# atmega.net
KiCad netlist of a schematic drawn in EAGLE
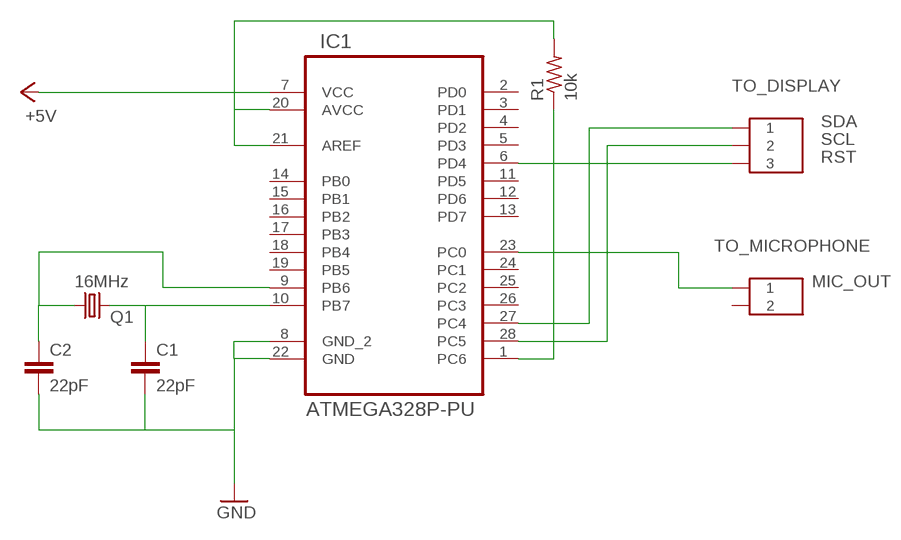
[diagram p0: schematic, sheet 1]

(export (version "E")
  (design (tool "Eeschema 10.0.6"))
  (components
    (comp (ref "C1")
      (value "22pF")
      (footprint "eagle-import:C025-024X044")
      (libsource (lib "eagle-import") (part "C-EU025-024X044"))
    )
    (comp (ref "C2")
      (value "22pF")
      (footprint "eagle-import:C025-024X044")
      (libsource (lib "eagle-import") (part "C-EU025-024X044"))
    )
    (comp (ref "IC1")
      (value "ATMEGA328P-PU")
      (footprint "eagle-import:DIP254P762X457-28")
      (libsource (lib "eagle-import") (part "ATMEGA328P-PU"))
    )
    (comp (ref "Q1")
      (value "16MHz")
      (footprint "eagle-import:86SMX")
      (libsource (lib "eagle-import") (part "CRYSTAL68SMX"))
    )
    (comp (ref "R1")
      (value "10k")
      (footprint "eagle-import:0204V")
      (libsource (lib "eagle-import") (part "R-US_0204/2V"))
    )
    (comp (ref "TO_DISPLAY")
      (value "EZG-00-303")
      (footprint "eagle-import:EZG-00-303")
      (libsource (lib "eagle-import") (part "EZG-?-30300"))
    )
    (comp (ref "TO_MICROPHONE")
      (value "EZG-00-302")
      (footprint "eagle-import:EZG-00-302")
      (libsource (lib "eagle-import") (part "EZG-?-30200"))
    )
  )
  (nets
    (net (code "1") (name "+5V") (class "Default")
      (node (ref "IC1") (pin "20") (pinfunction "AVCC_20") (pintype "power_in"))
      (node (ref "IC1") (pin "21") (pinfunction "AREF_21") (pintype "input"))
      (node (ref "IC1") (pin "7") (pinfunction "VCC_7") (pintype "power_in"))
      (node (ref "R1") (pin "2") (pinfunction "2_2") (pintype "passive"))
    )
    (net (code "2") (name "GND") (class "Default")
      (node (ref "C1") (pin "2") (pinfunction "2_2") (pintype "passive"))
      (node (ref "C2") (pin "2") (pinfunction "2_2") (pintype "passive"))
      (node (ref "IC1") (pin "22") (pinfunction "GND_22") (pintype "passive"))
      (node (ref "IC1") (pin "8") (pinfunction "GND_2_8") (pintype "passive"))
    )
    (net (code "3") (name "Net-(IC1-PB6)") (class "Default")
      (node (ref "C2") (pin "1") (pinfunction "1_1") (pintype "passive"))
      (node (ref "IC1") (pin "9") (pinfunction "PB6_9") (pintype "bidirectional"))
      (node (ref "Q1") (pin "1") (pinfunction "1_1") (pintype "passive"))
    )
    (net (code "4") (name "Net-(IC1-PB7)") (class "Default")
      (node (ref "C1") (pin "1") (pinfunction "1_1") (pintype "passive"))
      (node (ref "IC1") (pin "10") (pinfunction "PB7_10") (pintype "bidirectional"))
      (node (ref "Q1") (pin "4") (pinfunction "2_4") (pintype "passive"))
    )
    (net (code "5") (name "Net-(IC1-PC0)") (class "Default")
      (node (ref "IC1") (pin "23") (pinfunction "PC0_23") (pintype "bidirectional"))
      (node (ref "TO_MICROPHONE") (pin "1") (pinfunction "1_1") (pintype "passive"))
    )
    (net (code "6") (name "Net-(IC1-PC4)") (class "Default")
      (node (ref "IC1") (pin "27") (pinfunction "PC4_27") (pintype "bidirectional"))
      (node (ref "TO_DISPLAY") (pin "1") (pinfunction "1_1") (pintype "passive"))
    )
    (net (code "7") (name "Net-(IC1-PC5)") (class "Default")
      (node (ref "IC1") (pin "28") (pinfunction "PC5_28") (pintype "bidirectional"))
      (node (ref "TO_DISPLAY") (pin "2") (pinfunction "2_2") (pintype "passive"))
    )
    (net (code "8") (name "Net-(IC1-PC6)") (class "Default")
      (node (ref "IC1") (pin "1") (pinfunction "PC6_1") (pintype "bidirectional"))
      (node (ref "R1") (pin "1") (pinfunction "1_1") (pintype "passive"))
    )
    (net (code "9") (name "Net-(IC1-PD4)") (class "Default")
      (node (ref "IC1") (pin "6") (pinfunction "PD4_6") (pintype "bidirectional"))
      (node (ref "TO_DISPLAY") (pin "3") (pinfunction "3_3") (pintype "passive"))
    )
    (net (code "10") (name "unconnected-(IC1-PB0-Pad14)") (class "Default")
      (node (ref "IC1") (pin "14") (pinfunction "PB0_14") (pintype "bidirectional"))
    )
    (net (code "11") (name "unconnected-(IC1-PB1-Pad15)") (class "Default")
      (node (ref "IC1") (pin "15") (pinfunction "PB1_15") (pintype "bidirectional"))
    )
    (net (code "12") (name "unconnected-(IC1-PB2-Pad16)") (class "Default")
      (node (ref "IC1") (pin "16") (pinfunction "PB2_16") (pintype "bidirectional"))
    )
    (net (code "13") (name "unconnected-(IC1-PB3-Pad17)") (class "Default")
      (node (ref "IC1") (pin "17") (pinfunction "PB3_17") (pintype "bidirectional"))
    )
    (net (code "14") (name "unconnected-(IC1-PB4-Pad18)") (class "Default")
      (node (ref "IC1") (pin "18") (pinfunction "PB4_18") (pintype "bidirectional"))
    )
    (net (code "15") (name "unconnected-(IC1-PB5-Pad19)") (class "Default")
      (node (ref "IC1") (pin "19") (pinfunction "PB5_19") (pintype "bidirectional"))
    )
    (net (code "16") (name "unconnected-(IC1-PC1-Pad24)") (class "Default")
      (node (ref "IC1") (pin "24") (pinfunction "PC1_24") (pintype "bidirectional"))
    )
    (net (code "17") (name "unconnected-(IC1-PC2-Pad25)") (class "Default")
      (node (ref "IC1") (pin "25") (pinfunction "PC2_25") (pintype "bidirectional"))
    )
    (net (code "18") (name "unconnected-(IC1-PC3-Pad26)") (class "Default")
      (node (ref "IC1") (pin "26") (pinfunction "PC3_26") (pintype "bidirectional"))
    )
    (net (code "19") (name "unconnected-(IC1-PD0-Pad2)") (class "Default")
      (node (ref "IC1") (pin "2") (pinfunction "PD0_2") (pintype "bidirectional"))
    )
    (net (code "20") (name "unconnected-(IC1-PD1-Pad3)") (class "Default")
      (node (ref "IC1") (pin "3") (pinfunction "PD1_3") (pintype "bidirectional"))
    )
    (net (code "21") (name "unconnected-(IC1-PD2-Pad4)") (class "Default")
      (node (ref "IC1") (pin "4") (pinfunction "PD2_4") (pintype "bidirectional"))
    )
    (net (code "22") (name "unconnected-(IC1-PD3-Pad5)") (class "Default")
      (node (ref "IC1") (pin "5") (pinfunction "PD3_5") (pintype "bidirectional"))
    )
    (net (code "23") (name "unconnected-(IC1-PD5-Pad11)") (class "Default")
      (node (ref "IC1") (pin "11") (pinfunction "PD5_11") (pintype "bidirectional"))
    )
    (net (code "24") (name "unconnected-(IC1-PD6-Pad12)") (class "Default")
      (node (ref "IC1") (pin "12") (pinfunction "PD6_12") (pintype "bidirectional"))
    )
    (net (code "25") (name "unconnected-(IC1-PD7-Pad13)") (class "Default")
      (node (ref "IC1") (pin "13") (pinfunction "PD7_13") (pintype "bidirectional"))
    )
    (net (code "26") (name "unconnected-(TO_MICROPHONE-Pad2)") (class "Default")
      (node (ref "TO_MICROPHONE") (pin "2") (pinfunction "2_2") (pintype "passive"))
    )
  )
)
